# tester.net
KiCad netlist of a schematic drawn in EAGLE
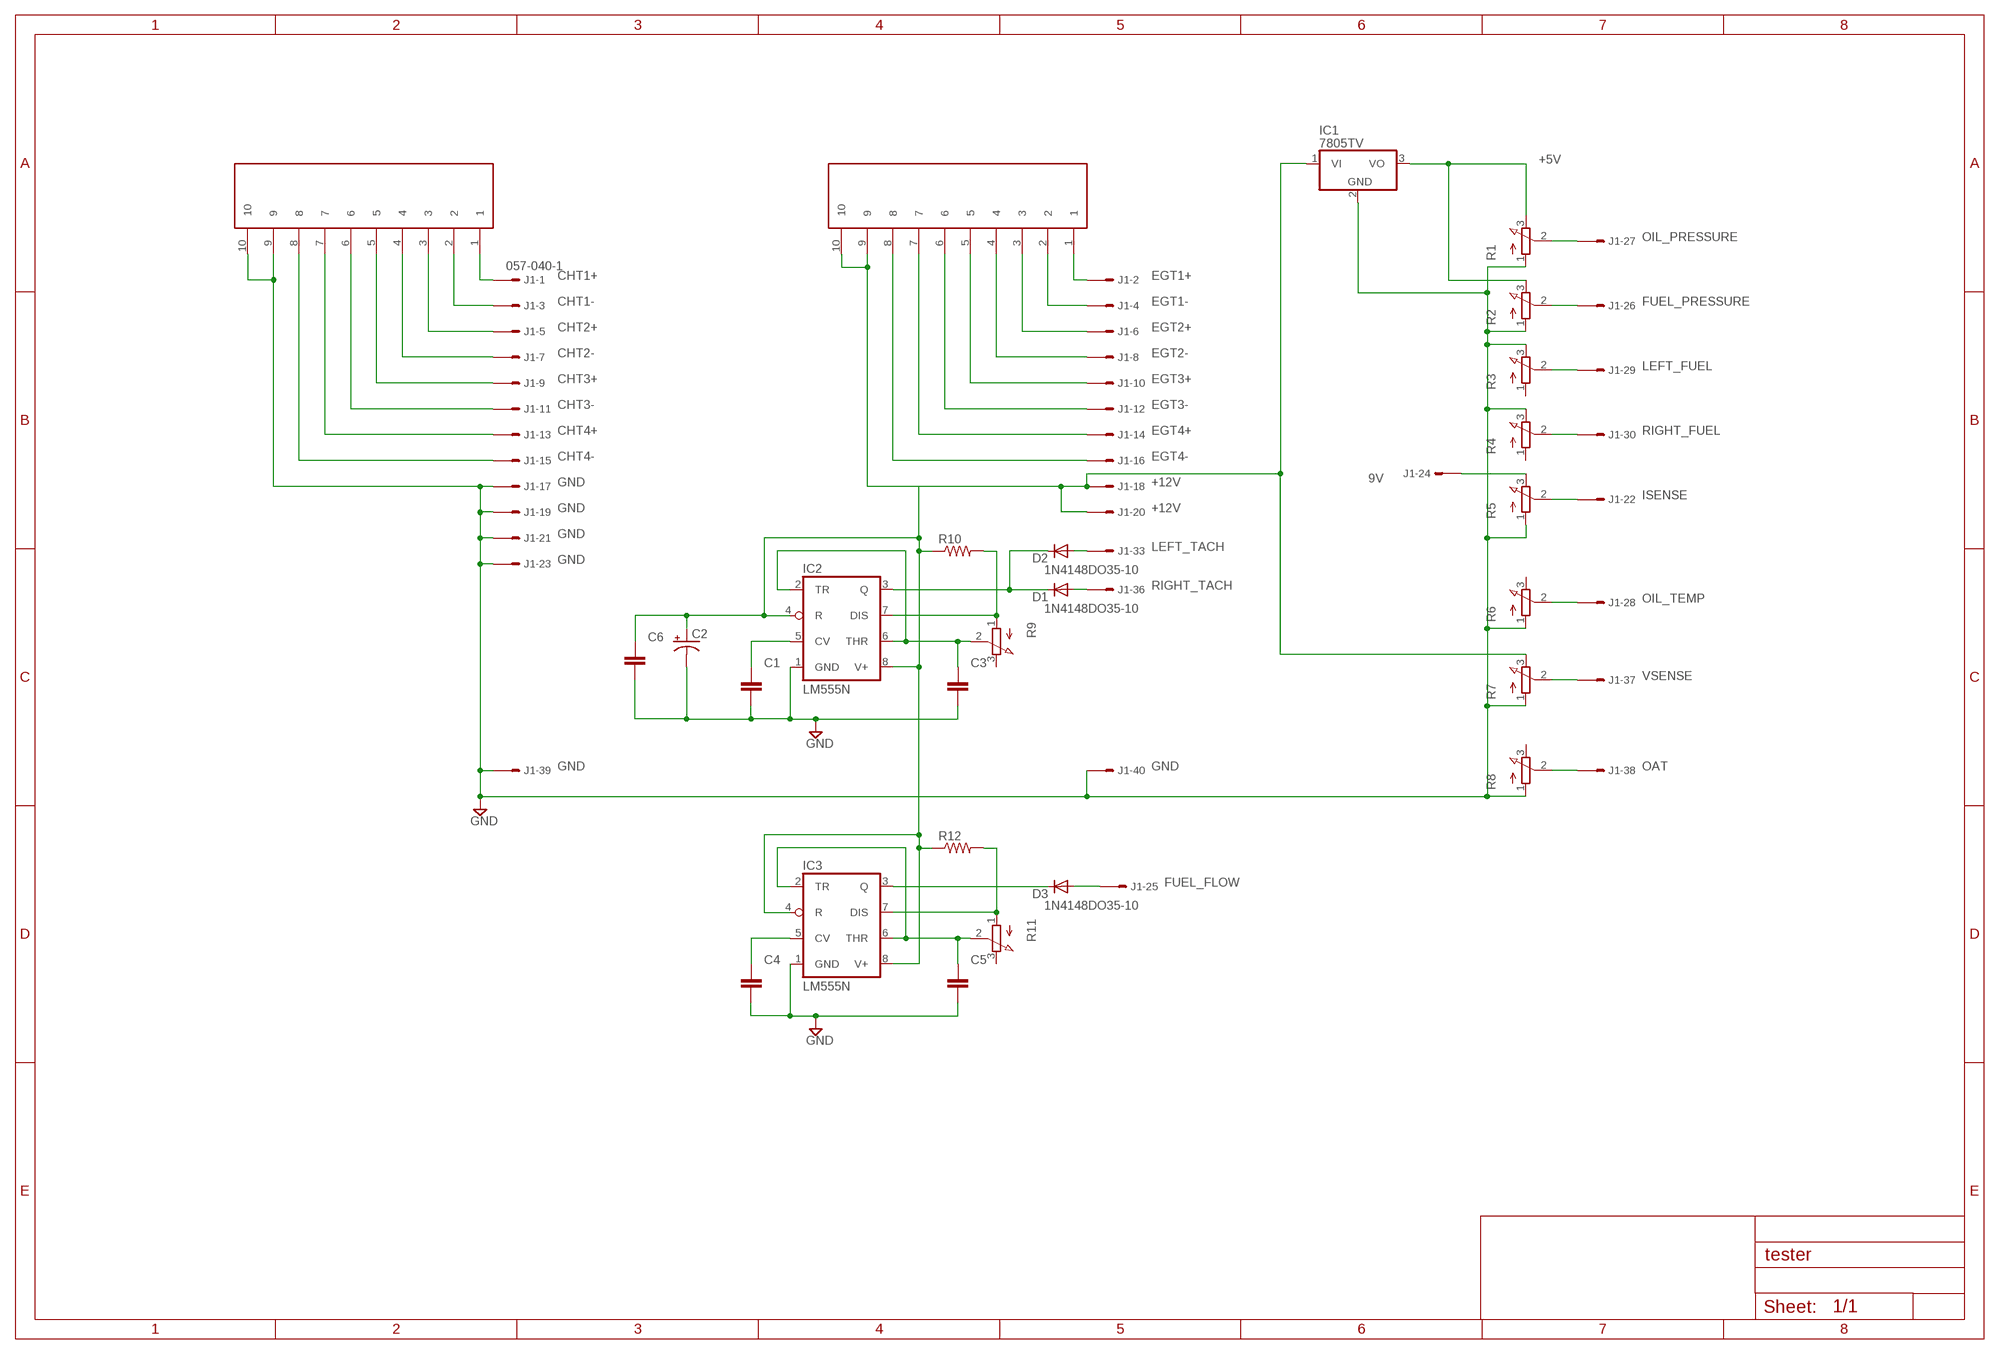
[diagram p0: schematic, sheet 1]

(export (version "E")
  (design (tool "Eeschema 10.0.6"))
  (components
    (comp (ref "C1")
      (value "CAPACITOR_NPOL-PTH_0.1\"")
      (footprint "eagle-import:C0.1PTH")
      (libsource (lib "eagle-import") (part "CAPACITOR_NPOL-PTH_0.1{dblquote}"))
    )
    (comp (ref "C2")
      (value "CAP_POLPTH2")
      (footprint "eagle-import:CPOL-RADIAL-10UF-25V")
      (libsource (lib "eagle-import") (part "CAP_POLPTH2"))
    )
    (comp (ref "C3")
      (value "CAPACITOR_NPOL-PTH_0.1\"")
      (footprint "eagle-import:C0.1PTH")
      (libsource (lib "eagle-import") (part "CAPACITOR_NPOL-PTH_0.1{dblquote}"))
    )
    (comp (ref "C4")
      (value "CAPACITOR_NPOL-PTH_0.1\"")
      (footprint "eagle-import:C0.1PTH")
      (libsource (lib "eagle-import") (part "CAPACITOR_NPOL-PTH_0.1{dblquote}"))
    )
    (comp (ref "C5")
      (value "CAPACITOR_NPOL-PTH_0.1\"")
      (footprint "eagle-import:C0.1PTH")
      (libsource (lib "eagle-import") (part "CAPACITOR_NPOL-PTH_0.1{dblquote}"))
    )
    (comp (ref "C6")
      (value "CAPACITOR_NPOL-PTH_0.1\"")
      (footprint "eagle-import:C0.1PTH")
      (libsource (lib "eagle-import") (part "CAPACITOR_NPOL-PTH_0.1{dblquote}"))
    )
    (comp (ref "D1")
      (value "1N4148DO35-10")
      (footprint "eagle-import:DO35-10")
      (libsource (lib "eagle-import") (part "1N4148DO35-10"))
    )
    (comp (ref "D2")
      (value "1N4148DO35-10")
      (footprint "eagle-import:DO35-10")
      (libsource (lib "eagle-import") (part "1N4148DO35-10"))
    )
    (comp (ref "D3")
      (value "1N4148DO35-10")
      (footprint "eagle-import:DO35-10")
      (libsource (lib "eagle-import") (part "1N4148DO35-10"))
    )
    (comp (ref "IC1")
      (value "7805TV")
      (footprint "eagle-import:TO220V")
      (libsource (lib "eagle-import") (part "78TV05"))
    )
    (comp (ref "IC2")
      (value "LM555N")
      (footprint "eagle-import:DIL08")
      (libsource (lib "eagle-import") (part "555NLM"))
    )
    (comp (ref "IC3")
      (value "LM555N")
      (footprint "eagle-import:DIL08")
      (libsource (lib "eagle-import") (part "555NLM"))
    )
    (comp (ref "J1")
      (value "057-040-1")
      (footprint "eagle-import:057-040-1")
      (fields (field (name "PARTNO") "SBH11-PBPC-D20-ST-BK"))
      (libsource (lib "eagle-import") (part "057-040-1"))
    )
    (comp (ref "R1")
      (value "3RP/1610N")
      (footprint "eagle-import:3RP_1610N")
      (libsource (lib "eagle-import") (part "3RP/1610N"))
    )
    (comp (ref "R2")
      (value "3RP/1610N")
      (footprint "eagle-import:3RP_1610N")
      (libsource (lib "eagle-import") (part "3RP/1610N"))
    )
    (comp (ref "R3")
      (value "3RP/1610N")
      (footprint "eagle-import:3RP_1610N")
      (libsource (lib "eagle-import") (part "3RP/1610N"))
    )
    (comp (ref "R4")
      (value "3RP/1610N")
      (footprint "eagle-import:3RP_1610N")
      (libsource (lib "eagle-import") (part "3RP/1610N"))
    )
    (comp (ref "R5")
      (value "3RP/1610N")
      (footprint "eagle-import:3RP_1610N")
      (libsource (lib "eagle-import") (part "3RP/1610N"))
    )
    (comp (ref "R6")
      (value "3RP/1610N")
      (footprint "eagle-import:3RP_1610N")
      (libsource (lib "eagle-import") (part "3RP/1610N"))
    )
    (comp (ref "R7")
      (value "3RP/1610N")
      (footprint "eagle-import:3RP_1610N")
      (libsource (lib "eagle-import") (part "3RP/1610N"))
    )
    (comp (ref "R8")
      (value "3RP/1610N")
      (footprint "eagle-import:3RP_1610N")
      (libsource (lib "eagle-import") (part "3RP/1610N"))
    )
    (comp (ref "R9")
      (value "3RP/1610N")
      (footprint "eagle-import:3RP_1610N")
      (libsource (lib "eagle-import") (part "3RP/1610N"))
    )
    (comp (ref "R10")
      (value "RESISTORPTH-1/4W")
      (footprint "eagle-import:AXIAL-0.4")
      (libsource (lib "eagle-import") (part "RESISTORPTH-1/4W"))
    )
    (comp (ref "R11")
      (value "3RP/1610N")
      (footprint "eagle-import:3RP_1610N")
      (libsource (lib "eagle-import") (part "3RP/1610N"))
    )
    (comp (ref "R12")
      (value "RESISTORPTH-1/4W")
      (footprint "eagle-import:AXIAL-0.4")
      (libsource (lib "eagle-import") (part "RESISTORPTH-1/4W"))
    )
    (comp (ref "TB2")
      (value "282847-10")
      (footprint "eagle-import:282847-10")
      (fields (field (name "PARTNO") "1-282847-0"))
      (libsource (lib "eagle-import") (part "282847-10"))
    )
    (comp (ref "TB4")
      (value "282847-10")
      (footprint "eagle-import:282847-10")
      (fields (field (name "PARTNO") "1-282847-0"))
      (libsource (lib "eagle-import") (part "282847-10"))
    )
  )
  (nets
    (net (code "1") (name "/+5V") (class "Default")
      (node (ref "IC1") (pin "3") (pinfunction "VO_3") (pintype "passive"))
      (node (ref "R1") (pin "3") (pinfunction "E_3") (pintype "passive"))
      (node (ref "R2") (pin "3") (pinfunction "E_3") (pintype "passive"))
    )
    (net (code "2") (name "/+12V") (class "Default")
      (node (ref "C2") (pin "1") (pinfunction "+_1") (pintype "passive"))
      (node (ref "C6") (pin "1") (pinfunction "1_1") (pintype "passive"))
      (node (ref "IC1") (pin "1") (pinfunction "VI_1") (pintype "input"))
      (node (ref "IC2") (pin "4") (pinfunction "R_4") (pintype "input"))
      (node (ref "IC2") (pin "8") (pinfunction "V+_8") (pintype "power_in"))
      (node (ref "IC3") (pin "4") (pinfunction "R_4") (pintype "input"))
      (node (ref "IC3") (pin "8") (pinfunction "V+_8") (pintype "power_in"))
      (node (ref "J1") (pin "18") (pinfunction "S_18") (pintype "passive"))
      (node (ref "J1") (pin "20") (pinfunction "S_20") (pintype "passive"))
      (node (ref "R10") (pin "P$1") (pinfunction "1_P$1") (pintype "passive"))
      (node (ref "R12") (pin "P$1") (pinfunction "1_P$1") (pintype "passive"))
      (node (ref "R7") (pin "3") (pinfunction "E_3") (pintype "passive"))
      (node (ref "TB4") (pin "10") (pinfunction "10_10") (pintype "bidirectional"))
      (node (ref "TB4") (pin "9") (pinfunction "9_9") (pintype "bidirectional"))
    )
    (net (code "3") (name "/9V") (class "Default")
      (node (ref "J1") (pin "24") (pinfunction "S_24") (pintype "passive"))
      (node (ref "R5") (pin "3") (pinfunction "E_3") (pintype "passive"))
    )
    (net (code "4") (name "/CHT1+") (class "Default")
      (node (ref "J1") (pin "1") (pinfunction "S_1") (pintype "passive"))
      (node (ref "TB2") (pin "1") (pinfunction "1_1") (pintype "bidirectional"))
    )
    (net (code "5") (name "/CHT1-") (class "Default")
      (node (ref "J1") (pin "3") (pinfunction "S_3") (pintype "passive"))
      (node (ref "TB2") (pin "2") (pinfunction "2_2") (pintype "bidirectional"))
    )
    (net (code "6") (name "/CHT2+") (class "Default")
      (node (ref "J1") (pin "5") (pinfunction "S_5") (pintype "passive"))
      (node (ref "TB2") (pin "3") (pinfunction "3_3") (pintype "bidirectional"))
    )
    (net (code "7") (name "/CHT2-") (class "Default")
      (node (ref "J1") (pin "7") (pinfunction "S_7") (pintype "passive"))
      (node (ref "TB2") (pin "4") (pinfunction "4_4") (pintype "bidirectional"))
    )
    (net (code "8") (name "/CHT3+") (class "Default")
      (node (ref "J1") (pin "9") (pinfunction "S_9") (pintype "passive"))
      (node (ref "TB2") (pin "5") (pinfunction "5_5") (pintype "bidirectional"))
    )
    (net (code "9") (name "/CHT3-") (class "Default")
      (node (ref "J1") (pin "11") (pinfunction "S_11") (pintype "passive"))
      (node (ref "TB2") (pin "6") (pinfunction "6_6") (pintype "bidirectional"))
    )
    (net (code "10") (name "/CHT4+") (class "Default")
      (node (ref "J1") (pin "13") (pinfunction "S_13") (pintype "passive"))
      (node (ref "TB2") (pin "7") (pinfunction "7_7") (pintype "bidirectional"))
    )
    (net (code "11") (name "/CHT4-") (class "Default")
      (node (ref "J1") (pin "15") (pinfunction "S_15") (pintype "passive"))
      (node (ref "TB2") (pin "8") (pinfunction "8_8") (pintype "bidirectional"))
    )
    (net (code "12") (name "/EGT1+") (class "Default")
      (node (ref "J1") (pin "2") (pinfunction "S_2") (pintype "passive"))
      (node (ref "TB4") (pin "1") (pinfunction "1_1") (pintype "bidirectional"))
    )
    (net (code "13") (name "/EGT1-") (class "Default")
      (node (ref "J1") (pin "4") (pinfunction "S_4") (pintype "passive"))
      (node (ref "TB4") (pin "2") (pinfunction "2_2") (pintype "bidirectional"))
    )
    (net (code "14") (name "/EGT2+") (class "Default")
      (node (ref "J1") (pin "6") (pinfunction "S_6") (pintype "passive"))
      (node (ref "TB4") (pin "3") (pinfunction "3_3") (pintype "bidirectional"))
    )
    (net (code "15") (name "/EGT2-") (class "Default")
      (node (ref "J1") (pin "8") (pinfunction "S_8") (pintype "passive"))
      (node (ref "TB4") (pin "4") (pinfunction "4_4") (pintype "bidirectional"))
    )
    (net (code "16") (name "/EGT3+") (class "Default")
      (node (ref "J1") (pin "10") (pinfunction "S_10") (pintype "passive"))
      (node (ref "TB4") (pin "5") (pinfunction "5_5") (pintype "bidirectional"))
    )
    (net (code "17") (name "/EGT3-") (class "Default")
      (node (ref "J1") (pin "12") (pinfunction "S_12") (pintype "passive"))
      (node (ref "TB4") (pin "6") (pinfunction "6_6") (pintype "bidirectional"))
    )
    (net (code "18") (name "/EGT4+") (class "Default")
      (node (ref "J1") (pin "14") (pinfunction "S_14") (pintype "passive"))
      (node (ref "TB4") (pin "7") (pinfunction "7_7") (pintype "bidirectional"))
    )
    (net (code "19") (name "/EGT4-") (class "Default")
      (node (ref "J1") (pin "16") (pinfunction "S_16") (pintype "passive"))
      (node (ref "TB4") (pin "8") (pinfunction "8_8") (pintype "bidirectional"))
    )
    (net (code "20") (name "/FUEL_FLOW") (class "Default")
      (node (ref "D3") (pin "A") (pinfunction "A_A") (pintype "passive"))
      (node (ref "J1") (pin "25") (pinfunction "S_25") (pintype "passive"))
    )
    (net (code "21") (name "/FUEL_PRESSURE") (class "Default")
      (node (ref "J1") (pin "26") (pinfunction "S_26") (pintype "passive"))
      (node (ref "R2") (pin "2") (pinfunction "S_2") (pintype "passive"))
    )
    (net (code "22") (name "/ISENSE") (class "Default")
      (node (ref "J1") (pin "22") (pinfunction "S_22") (pintype "passive"))
      (node (ref "R5") (pin "2") (pinfunction "S_2") (pintype "passive"))
    )
    (net (code "23") (name "/LEFT_FUEL") (class "Default")
      (node (ref "J1") (pin "29") (pinfunction "S_29") (pintype "passive"))
      (node (ref "R3") (pin "2") (pinfunction "S_2") (pintype "passive"))
    )
    (net (code "24") (name "/LEFT_TACH") (class "Default")
      (node (ref "D2") (pin "A") (pinfunction "A_A") (pintype "passive"))
      (node (ref "J1") (pin "33") (pinfunction "S_33") (pintype "passive"))
    )
    (net (code "25") (name "/OAT") (class "Default")
      (node (ref "J1") (pin "38") (pinfunction "S_38") (pintype "passive"))
      (node (ref "R8") (pin "2") (pinfunction "S_2") (pintype "passive"))
    )
    (net (code "26") (name "/OIL_PRESSURE") (class "Default")
      (node (ref "J1") (pin "27") (pinfunction "S_27") (pintype "passive"))
      (node (ref "R1") (pin "2") (pinfunction "S_2") (pintype "passive"))
    )
    (net (code "27") (name "/OIL_TEMP") (class "Default")
      (node (ref "J1") (pin "28") (pinfunction "S_28") (pintype "passive"))
      (node (ref "R6") (pin "2") (pinfunction "S_2") (pintype "passive"))
    )
    (net (code "28") (name "/RIGHT_FUEL") (class "Default")
      (node (ref "J1") (pin "30") (pinfunction "S_30") (pintype "passive"))
      (node (ref "R4") (pin "2") (pinfunction "S_2") (pintype "passive"))
    )
    (net (code "29") (name "/RIGHT_TACH") (class "Default")
      (node (ref "D1") (pin "A") (pinfunction "A_A") (pintype "passive"))
      (node (ref "J1") (pin "36") (pinfunction "S_36") (pintype "passive"))
    )
    (net (code "30") (name "/VSENSE") (class "Default")
      (node (ref "J1") (pin "37") (pinfunction "S_37") (pintype "passive"))
      (node (ref "R7") (pin "2") (pinfunction "S_2") (pintype "passive"))
    )
    (net (code "31") (name "GND") (class "Default")
      (node (ref "C1") (pin "2") (pinfunction "2_2") (pintype "passive"))
      (node (ref "C2") (pin "2") (pinfunction "-_2") (pintype "passive"))
      (node (ref "C3") (pin "2") (pinfunction "2_2") (pintype "passive"))
      (node (ref "C4") (pin "2") (pinfunction "2_2") (pintype "passive"))
      (node (ref "C5") (pin "2") (pinfunction "2_2") (pintype "passive"))
      (node (ref "C6") (pin "2") (pinfunction "2_2") (pintype "passive"))
      (node (ref "IC1") (pin "2") (pinfunction "GND_2") (pintype "passive"))
      (node (ref "IC2") (pin "1") (pinfunction "GND_1") (pintype "power_in"))
      (node (ref "IC3") (pin "1") (pinfunction "GND_1") (pintype "power_in"))
      (node (ref "J1") (pin "17") (pinfunction "S_17") (pintype "passive"))
      (node (ref "J1") (pin "19") (pinfunction "S_19") (pintype "passive"))
      (node (ref "J1") (pin "21") (pinfunction "S_21") (pintype "passive"))
      (node (ref "J1") (pin "23") (pinfunction "S_23") (pintype "passive"))
      (node (ref "J1") (pin "39") (pinfunction "S_39") (pintype "passive"))
      (node (ref "J1") (pin "40") (pinfunction "S_40") (pintype "passive"))
      (node (ref "R1") (pin "1") (pinfunction "A_1") (pintype "passive"))
      (node (ref "R2") (pin "1") (pinfunction "A_1") (pintype "passive"))
      (node (ref "R3") (pin "3") (pinfunction "E_3") (pintype "passive"))
      (node (ref "R4") (pin "3") (pinfunction "E_3") (pintype "passive"))
      (node (ref "R5") (pin "1") (pinfunction "A_1") (pintype "passive"))
      (node (ref "R6") (pin "1") (pinfunction "A_1") (pintype "passive"))
      (node (ref "R7") (pin "1") (pinfunction "A_1") (pintype "passive"))
      (node (ref "R8") (pin "1") (pinfunction "A_1") (pintype "passive"))
      (node (ref "TB2") (pin "10") (pinfunction "10_10") (pintype "bidirectional"))
      (node (ref "TB2") (pin "9") (pinfunction "9_9") (pintype "bidirectional"))
    )
    (net (code "32") (name "Net-(IC2-CV)") (class "Default")
      (node (ref "C1") (pin "1") (pinfunction "1_1") (pintype "passive"))
      (node (ref "IC2") (pin "5") (pinfunction "CV_5") (pintype "input"))
    )
    (net (code "33") (name "Net-(IC2-DIS)") (class "Default")
      (node (ref "IC2") (pin "7") (pinfunction "DIS_7") (pintype "input"))
      (node (ref "R10") (pin "P$2") (pinfunction "2_P$2") (pintype "passive"))
      (node (ref "R9") (pin "1") (pinfunction "A_1") (pintype "passive"))
    )
    (net (code "34") (name "Net-(IC2-Q)") (class "Default")
      (node (ref "D1") (pin "C") (pinfunction "C_C") (pintype "passive"))
      (node (ref "D2") (pin "C") (pinfunction "C_C") (pintype "passive"))
      (node (ref "IC2") (pin "3") (pinfunction "Q_3") (pintype "output"))
    )
    (net (code "35") (name "Net-(IC2-THR)") (class "Default")
      (node (ref "C3") (pin "1") (pinfunction "1_1") (pintype "passive"))
      (node (ref "IC2") (pin "2") (pinfunction "TR_2") (pintype "input"))
      (node (ref "IC2") (pin "6") (pinfunction "THR_6") (pintype "input"))
      (node (ref "R9") (pin "2") (pinfunction "S_2") (pintype "passive"))
    )
    (net (code "36") (name "Net-(IC3-CV)") (class "Default")
      (node (ref "C4") (pin "1") (pinfunction "1_1") (pintype "passive"))
      (node (ref "IC3") (pin "5") (pinfunction "CV_5") (pintype "input"))
    )
    (net (code "37") (name "Net-(IC3-DIS)") (class "Default")
      (node (ref "IC3") (pin "7") (pinfunction "DIS_7") (pintype "input"))
      (node (ref "R11") (pin "1") (pinfunction "A_1") (pintype "passive"))
      (node (ref "R12") (pin "P$2") (pinfunction "2_P$2") (pintype "passive"))
    )
    (net (code "38") (name "Net-(IC3-Q)") (class "Default")
      (node (ref "D3") (pin "C") (pinfunction "C_C") (pintype "passive"))
      (node (ref "IC3") (pin "3") (pinfunction "Q_3") (pintype "output"))
    )
    (net (code "39") (name "Net-(IC3-THR)") (class "Default")
      (node (ref "C5") (pin "1") (pinfunction "1_1") (pintype "passive"))
      (node (ref "IC3") (pin "2") (pinfunction "TR_2") (pintype "input"))
      (node (ref "IC3") (pin "6") (pinfunction "THR_6") (pintype "input"))
      (node (ref "R11") (pin "2") (pinfunction "S_2") (pintype "passive"))
    )
    (net (code "40") (name "unconnected-(R3-A-Pad1)") (class "Default")
      (node (ref "R3") (pin "1") (pinfunction "A_1") (pintype "passive"))
    )
    (net (code "41") (name "unconnected-(R4-A-Pad1)") (class "Default")
      (node (ref "R4") (pin "1") (pinfunction "A_1") (pintype "passive"))
    )
    (net (code "42") (name "unconnected-(R6-E-Pad3)") (class "Default")
      (node (ref "R6") (pin "3") (pinfunction "E_3") (pintype "passive"))
    )
    (net (code "43") (name "unconnected-(R8-E-Pad3)") (class "Default")
      (node (ref "R8") (pin "3") (pinfunction "E_3") (pintype "passive"))
    )
    (net (code "44") (name "unconnected-(R9-E-Pad3)") (class "Default")
      (node (ref "R9") (pin "3") (pinfunction "E_3") (pintype "passive"))
    )
    (net (code "45") (name "unconnected-(R11-E-Pad3)") (class "Default")
      (node (ref "R11") (pin "3") (pinfunction "E_3") (pintype "passive"))
    )
  )
)
